# camera.net
KiCad netlist of a schematic drawn in Altium Designer
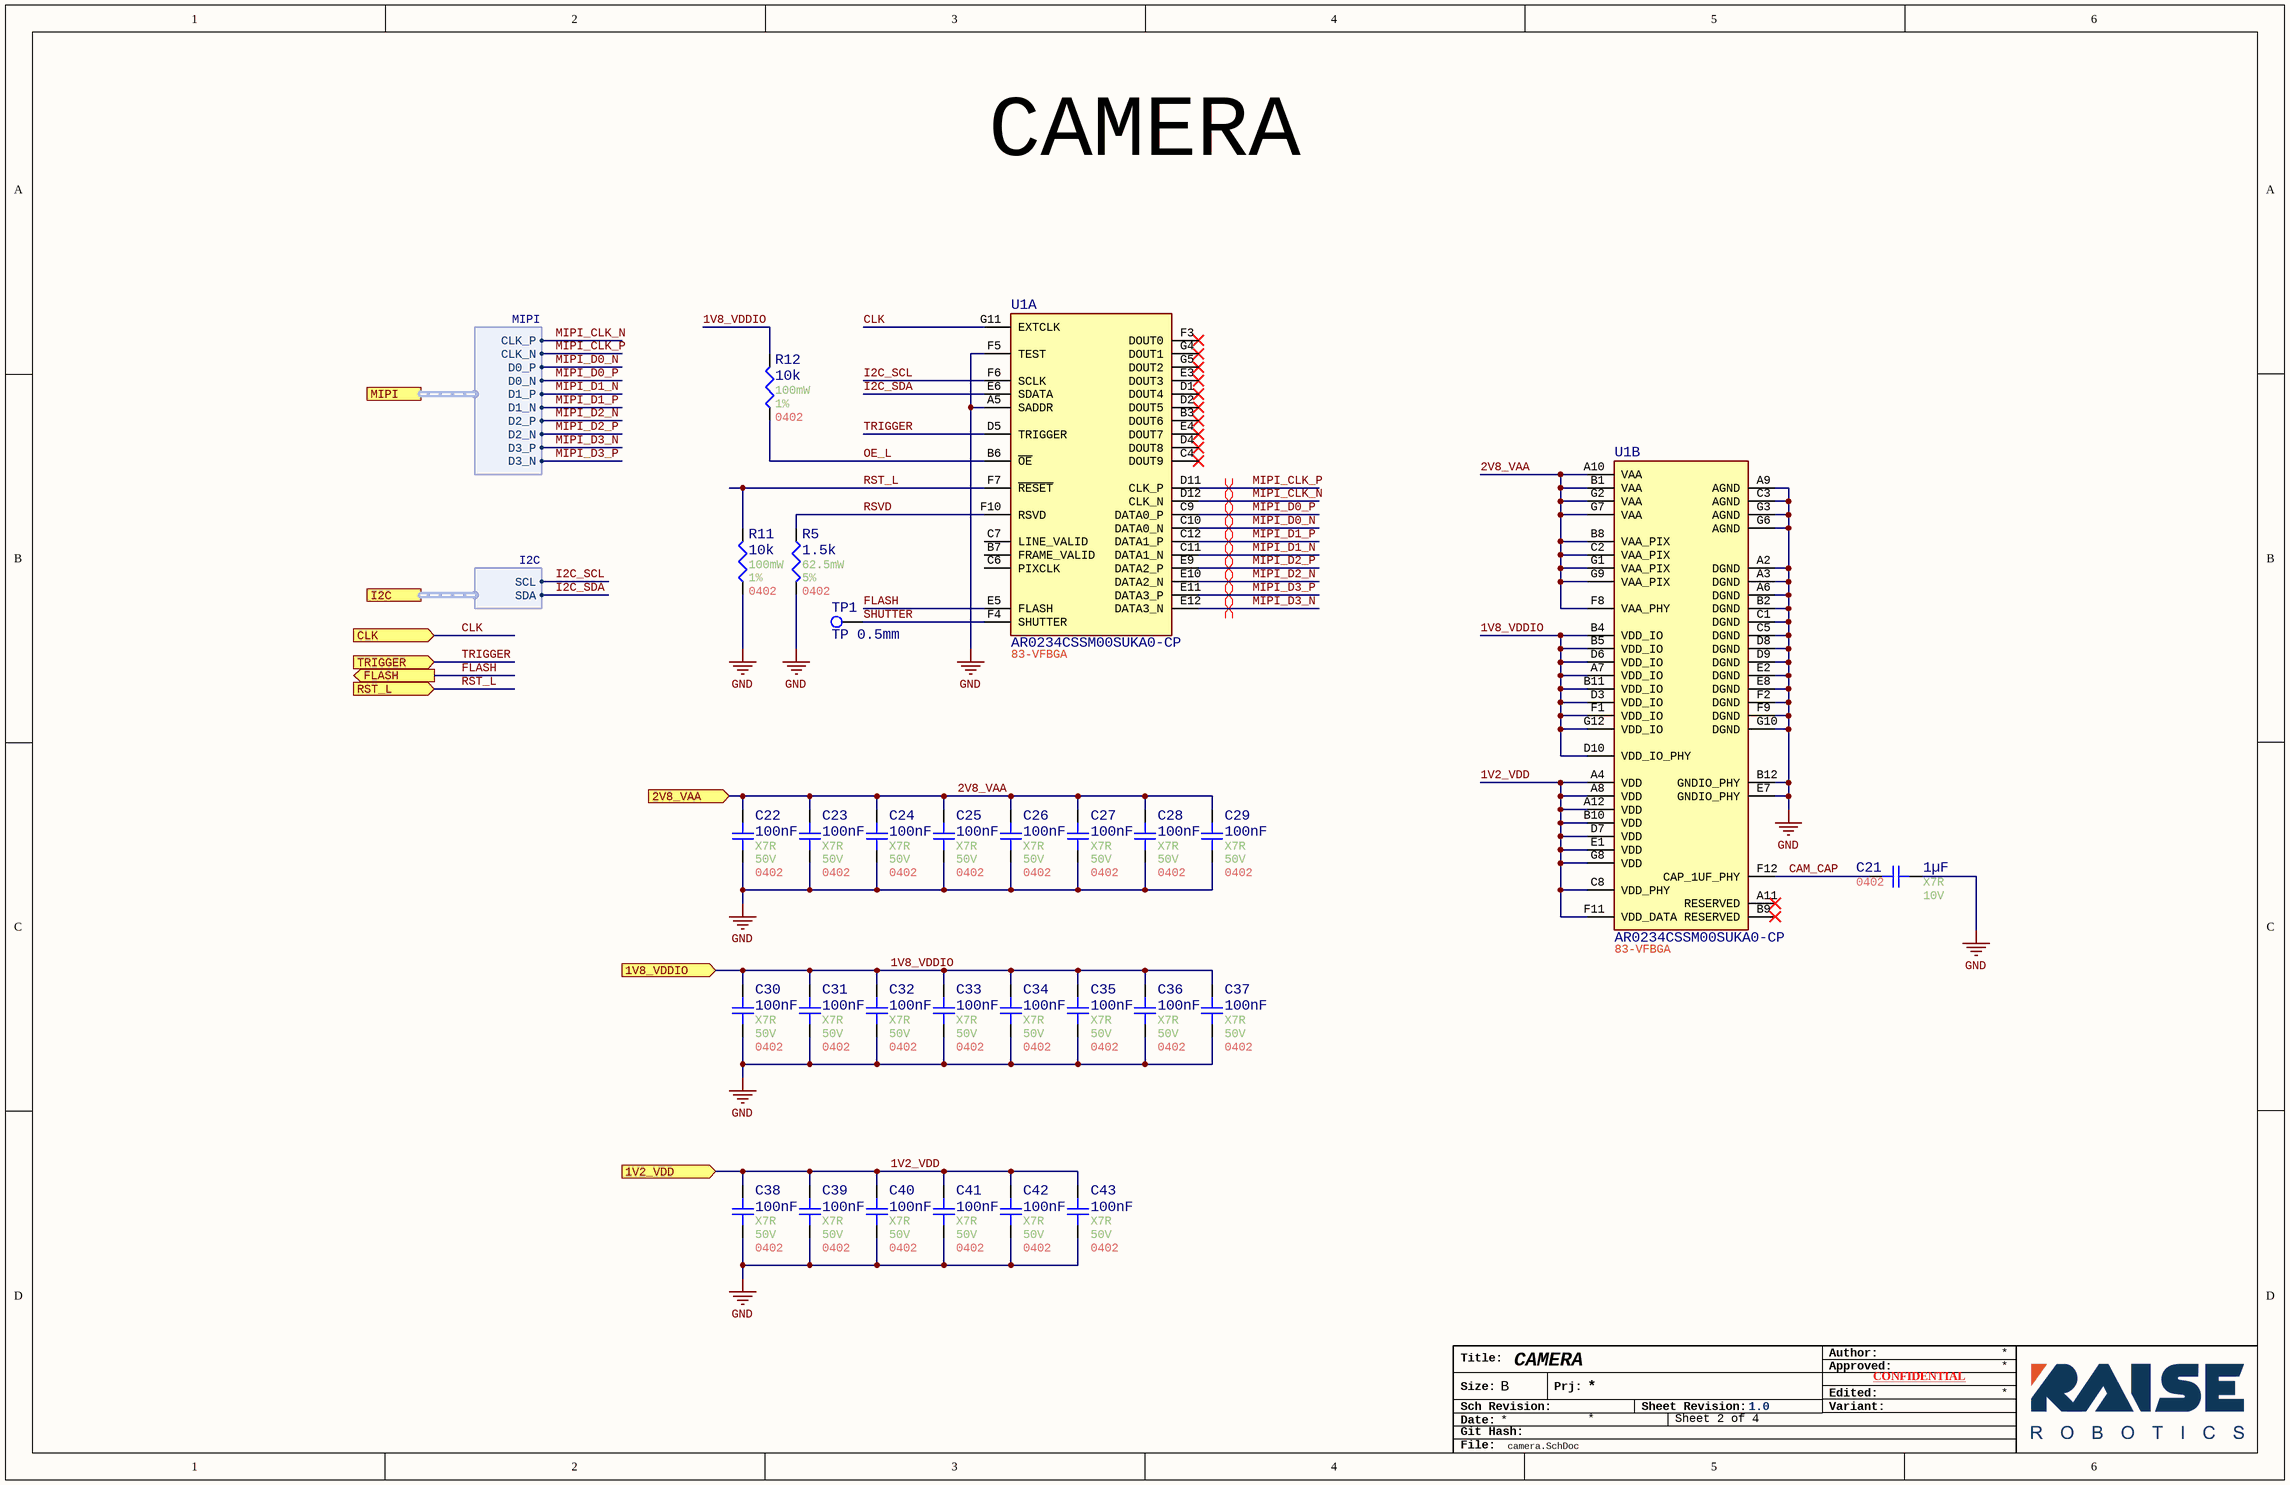
[diagram p0: camera.SchDoc]

(export (version "E")
  (design (tool "Eeschema 10.0.6"))
  (components
    (comp (ref "C21")
      (value "1µF")
      (footprint "Generic 0402 capacitor")
      (description "Cap Cer 1UF 20V X7T 0402")
      (fields
        (field (name "TEMPERATURE COEFFICIENT") "X7R")
        (field (name "VOLTAGE RATING") "10V")
        (field (name "CASE/PACKAGE") "0402")
        (field (name "TOLERANCE") "20%")
        (field (name "Comment") "MAASL105CD7105MFCA01")
      )
      (libsource (lib "Raise Robotics") (part "Unpolarized Capacitor"))
    )
    (comp (ref "C22")
      (value "100nF")
      (footprint "Generic 0402 capacitor")
      (fields
        (field (name "TEMPERATURE COEFFICIENT") "X7R")
        (field (name "VOLTAGE RATING") "50V")
        (field (name "CASE/PACKAGE") "0402")
        (field (name "TOLERANCE") "10%")
        (field (name "Comment") "GRT155R71H104KE01D")
      )
      (libsource (lib "Raise Robotics") (part "Unpolarized Capacitor"))
    )
    (comp (ref "C23")
      (value "100nF")
      (footprint "Generic 0402 capacitor")
      (fields
        (field (name "TEMPERATURE COEFFICIENT") "X7R")
        (field (name "VOLTAGE RATING") "50V")
        (field (name "CASE/PACKAGE") "0402")
        (field (name "TOLERANCE") "10%")
        (field (name "Comment") "GRT155R71H104KE01D")
      )
      (libsource (lib "Raise Robotics") (part "Unpolarized Capacitor"))
    )
    (comp (ref "C24")
      (value "100nF")
      (footprint "Generic 0402 capacitor")
      (fields
        (field (name "TEMPERATURE COEFFICIENT") "X7R")
        (field (name "VOLTAGE RATING") "50V")
        (field (name "CASE/PACKAGE") "0402")
        (field (name "TOLERANCE") "10%")
        (field (name "Comment") "GRT155R71H104KE01D")
      )
      (libsource (lib "Raise Robotics") (part "Unpolarized Capacitor"))
    )
    (comp (ref "C25")
      (value "100nF")
      (footprint "Generic 0402 capacitor")
      (fields
        (field (name "TEMPERATURE COEFFICIENT") "X7R")
        (field (name "VOLTAGE RATING") "50V")
        (field (name "CASE/PACKAGE") "0402")
        (field (name "TOLERANCE") "10%")
        (field (name "Comment") "GRT155R71H104KE01D")
      )
      (libsource (lib "Raise Robotics") (part "Unpolarized Capacitor"))
    )
    (comp (ref "C26")
      (value "100nF")
      (footprint "Generic 0402 capacitor")
      (fields
        (field (name "TEMPERATURE COEFFICIENT") "X7R")
        (field (name "VOLTAGE RATING") "50V")
        (field (name "CASE/PACKAGE") "0402")
        (field (name "TOLERANCE") "10%")
        (field (name "Comment") "GRT155R71H104KE01D")
      )
      (libsource (lib "Raise Robotics") (part "Unpolarized Capacitor"))
    )
    (comp (ref "C27")
      (value "100nF")
      (footprint "Generic 0402 capacitor")
      (fields
        (field (name "TEMPERATURE COEFFICIENT") "X7R")
        (field (name "VOLTAGE RATING") "50V")
        (field (name "CASE/PACKAGE") "0402")
        (field (name "TOLERANCE") "10%")
        (field (name "Comment") "GRT155R71H104KE01D")
      )
      (libsource (lib "Raise Robotics") (part "Unpolarized Capacitor"))
    )
    (comp (ref "C28")
      (value "100nF")
      (footprint "Generic 0402 capacitor")
      (fields
        (field (name "TEMPERATURE COEFFICIENT") "X7R")
        (field (name "VOLTAGE RATING") "50V")
        (field (name "CASE/PACKAGE") "0402")
        (field (name "TOLERANCE") "10%")
        (field (name "Comment") "GRT155R71H104KE01D")
      )
      (libsource (lib "Raise Robotics") (part "Unpolarized Capacitor"))
    )
    (comp (ref "C29")
      (value "100nF")
      (footprint "Generic 0402 capacitor")
      (fields
        (field (name "TEMPERATURE COEFFICIENT") "X7R")
        (field (name "VOLTAGE RATING") "50V")
        (field (name "CASE/PACKAGE") "0402")
        (field (name "TOLERANCE") "10%")
        (field (name "Comment") "GRT155R71H104KE01D")
      )
      (libsource (lib "Raise Robotics") (part "Unpolarized Capacitor"))
    )
    (comp (ref "C30")
      (value "100nF")
      (footprint "Generic 0402 capacitor")
      (fields
        (field (name "TEMPERATURE COEFFICIENT") "X7R")
        (field (name "VOLTAGE RATING") "50V")
        (field (name "CASE/PACKAGE") "0402")
        (field (name "TOLERANCE") "10%")
        (field (name "Comment") "GRT155R71H104KE01D")
      )
      (libsource (lib "Raise Robotics") (part "Unpolarized Capacitor"))
    )
    (comp (ref "C31")
      (value "100nF")
      (footprint "Generic 0402 capacitor")
      (fields
        (field (name "TEMPERATURE COEFFICIENT") "X7R")
        (field (name "VOLTAGE RATING") "50V")
        (field (name "CASE/PACKAGE") "0402")
        (field (name "TOLERANCE") "10%")
        (field (name "Comment") "GRT155R71H104KE01D")
      )
      (libsource (lib "Raise Robotics") (part "Unpolarized Capacitor"))
    )
    (comp (ref "C32")
      (value "100nF")
      (footprint "Generic 0402 capacitor")
      (fields
        (field (name "TEMPERATURE COEFFICIENT") "X7R")
        (field (name "VOLTAGE RATING") "50V")
        (field (name "CASE/PACKAGE") "0402")
        (field (name "TOLERANCE") "10%")
        (field (name "Comment") "GRT155R71H104KE01D")
      )
      (libsource (lib "Raise Robotics") (part "Unpolarized Capacitor"))
    )
    (comp (ref "C33")
      (value "100nF")
      (footprint "Generic 0402 capacitor")
      (fields
        (field (name "TEMPERATURE COEFFICIENT") "X7R")
        (field (name "VOLTAGE RATING") "50V")
        (field (name "CASE/PACKAGE") "0402")
        (field (name "TOLERANCE") "10%")
        (field (name "Comment") "GRT155R71H104KE01D")
      )
      (libsource (lib "Raise Robotics") (part "Unpolarized Capacitor"))
    )
    (comp (ref "C34")
      (value "100nF")
      (footprint "Generic 0402 capacitor")
      (fields
        (field (name "TEMPERATURE COEFFICIENT") "X7R")
        (field (name "VOLTAGE RATING") "50V")
        (field (name "CASE/PACKAGE") "0402")
        (field (name "TOLERANCE") "10%")
        (field (name "Comment") "GRT155R71H104KE01D")
      )
      (libsource (lib "Raise Robotics") (part "Unpolarized Capacitor"))
    )
    (comp (ref "C35")
      (value "100nF")
      (footprint "Generic 0402 capacitor")
      (fields
        (field (name "TEMPERATURE COEFFICIENT") "X7R")
        (field (name "VOLTAGE RATING") "50V")
        (field (name "CASE/PACKAGE") "0402")
        (field (name "TOLERANCE") "10%")
        (field (name "Comment") "GRT155R71H104KE01D")
      )
      (libsource (lib "Raise Robotics") (part "Unpolarized Capacitor"))
    )
    (comp (ref "C36")
      (value "100nF")
      (footprint "Generic 0402 capacitor")
      (fields
        (field (name "TEMPERATURE COEFFICIENT") "X7R")
        (field (name "VOLTAGE RATING") "50V")
        (field (name "CASE/PACKAGE") "0402")
        (field (name "TOLERANCE") "10%")
        (field (name "Comment") "GRT155R71H104KE01D")
      )
      (libsource (lib "Raise Robotics") (part "Unpolarized Capacitor"))
    )
    (comp (ref "C37")
      (value "100nF")
      (footprint "Generic 0402 capacitor")
      (fields
        (field (name "TEMPERATURE COEFFICIENT") "X7R")
        (field (name "VOLTAGE RATING") "50V")
        (field (name "CASE/PACKAGE") "0402")
        (field (name "TOLERANCE") "10%")
        (field (name "Comment") "GRT155R71H104KE01D")
      )
      (libsource (lib "Raise Robotics") (part "Unpolarized Capacitor"))
    )
    (comp (ref "C38")
      (value "100nF")
      (footprint "Generic 0402 capacitor")
      (fields
        (field (name "TEMPERATURE COEFFICIENT") "X7R")
        (field (name "VOLTAGE RATING") "50V")
        (field (name "CASE/PACKAGE") "0402")
        (field (name "TOLERANCE") "10%")
        (field (name "Comment") "GRT155R71H104KE01D")
      )
      (libsource (lib "Raise Robotics") (part "Unpolarized Capacitor"))
    )
    (comp (ref "C39")
      (value "100nF")
      (footprint "Generic 0402 capacitor")
      (fields
        (field (name "TEMPERATURE COEFFICIENT") "X7R")
        (field (name "VOLTAGE RATING") "50V")
        (field (name "CASE/PACKAGE") "0402")
        (field (name "TOLERANCE") "10%")
        (field (name "Comment") "GRT155R71H104KE01D")
      )
      (libsource (lib "Raise Robotics") (part "Unpolarized Capacitor"))
    )
    (comp (ref "C40")
      (value "100nF")
      (footprint "Generic 0402 capacitor")
      (fields
        (field (name "TEMPERATURE COEFFICIENT") "X7R")
        (field (name "VOLTAGE RATING") "50V")
        (field (name "CASE/PACKAGE") "0402")
        (field (name "TOLERANCE") "10%")
        (field (name "Comment") "GRT155R71H104KE01D")
      )
      (libsource (lib "Raise Robotics") (part "Unpolarized Capacitor"))
    )
    (comp (ref "C41")
      (value "100nF")
      (footprint "Generic 0402 capacitor")
      (fields
        (field (name "TEMPERATURE COEFFICIENT") "X7R")
        (field (name "VOLTAGE RATING") "50V")
        (field (name "CASE/PACKAGE") "0402")
        (field (name "TOLERANCE") "10%")
        (field (name "Comment") "GRT155R71H104KE01D")
      )
      (libsource (lib "Raise Robotics") (part "Unpolarized Capacitor"))
    )
    (comp (ref "C42")
      (value "100nF")
      (footprint "Generic 0402 capacitor")
      (fields
        (field (name "TEMPERATURE COEFFICIENT") "X7R")
        (field (name "VOLTAGE RATING") "50V")
        (field (name "CASE/PACKAGE") "0402")
        (field (name "TOLERANCE") "10%")
        (field (name "Comment") "GRT155R71H104KE01D")
      )
      (libsource (lib "Raise Robotics") (part "Unpolarized Capacitor"))
    )
    (comp (ref "C43")
      (value "100nF")
      (footprint "Generic 0402 capacitor")
      (fields
        (field (name "TEMPERATURE COEFFICIENT") "X7R")
        (field (name "VOLTAGE RATING") "50V")
        (field (name "CASE/PACKAGE") "0402")
        (field (name "TOLERANCE") "10%")
        (field (name "Comment") "GRT155R71H104KE01D")
      )
      (libsource (lib "Raise Robotics") (part "Unpolarized Capacitor"))
    )
    (comp (ref "R5")
      (value "1.5k")
      (footprint "Generic 0402 Resistor")
      (description "Res Thick Film 0402 1.5K Ohm 5% 0.063W ±100ppm/°C Molded SMD Paper T/R")
      (fields
        (field (name "POWER") "62.5mW")
        (field (name "TOLERANCE") "5%")
        (field (name "CASE/PACKAGE") "0402")
        (field (name "Comment") "RMCF0402JT1K50")
      )
      (libsource (lib "Raise Robotics") (part "Resistor"))
    )
    (comp (ref "R11")
      (value "10k")
      (footprint "Generic 0402 Resistor")
      (description "Fixed Resistor, Thin Film, 0.1W, 10000ohm, 50V, 1% +/-Tol, 100ppm/Cel, Surface Mount, 0402")
      (fields
        (field (name "POWER") "100mW")
        (field (name "TOLERANCE") "1%")
        (field (name "CASE/PACKAGE") "0402")
        (field (name "MANUFACTURER PART NUMBER") "Blank")
        (field (name "Comment") "RNCP0402FTD10K0")
      )
      (libsource (lib "Raise Robotics") (part "Resistor"))
    )
    (comp (ref "R12")
      (value "10k")
      (footprint "Generic 0402 Resistor")
      (description "Fixed Resistor, Thin Film, 0.1W, 10000ohm, 50V, 1% +/-Tol, 100ppm/Cel, Surface Mount, 0402")
      (fields
        (field (name "POWER") "100mW")
        (field (name "TOLERANCE") "1%")
        (field (name "CASE/PACKAGE") "0402")
        (field (name "MANUFACTURER PART NUMBER") "Blank")
        (field (name "Comment") "RNCP0402FTD10K0")
      )
      (libsource (lib "Raise Robotics") (part "Resistor"))
    )
    (comp (ref "TP1")
      (value "TP 0.5mm")
      (footprint "TP 0.5mm")
      (description "0.5mm circular test point")
      (libsource (lib "Raise Robotics") (part "Test Point"))
    )
    (comp (ref "U1")
      (value "AR0234CSSM00SUKA0-CP")
      (footprint "83-VFBGA")
      (description "1/2.6-inch 2.3 Mp CMOS Digital Image Sensor with Global Shutter 2.3MP 1/2.6, Mono, 0 deg CRA")
      (fields (field (name "MPN") "TJA1051TK/3/1J") (field (name "CASE/PACKAGE") "83-VFBGA"))
      (libsource (lib "Raise Robotics") (part "AR0234CSSM00SUKA0-CP"))
    )
  )
  (nets
    (net (code "3") (name "/1V2_VDD") (class "Default")
      (node (ref "C38") (pin "2") (pinfunction "2_2") (pintype "passive"))
      (node (ref "C39") (pin "2") (pinfunction "2_2") (pintype "passive"))
      (node (ref "C40") (pin "2") (pinfunction "2_2") (pintype "passive"))
      (node (ref "C41") (pin "2") (pinfunction "2_2") (pintype "passive"))
      (node (ref "C42") (pin "2") (pinfunction "2_2") (pintype "passive"))
      (node (ref "C43") (pin "2") (pinfunction "2_2") (pintype "passive"))
      (node (ref "U1") (pin "A12") (pinfunction "VDD_A12") (pintype "passive"))
      (node (ref "U1") (pin "A4") (pinfunction "VDD_A4") (pintype "passive"))
      (node (ref "U1") (pin "A8") (pinfunction "VDD_A8") (pintype "passive"))
      (node (ref "U1") (pin "B10") (pinfunction "VDD_B10") (pintype "passive"))
      (node (ref "U1") (pin "C8") (pinfunction "VDD_PHY_C8") (pintype "passive"))
      (node (ref "U1") (pin "D7") (pinfunction "VDD_D7") (pintype "passive"))
      (node (ref "U1") (pin "E1") (pinfunction "VDD_E1") (pintype "passive"))
      (node (ref "U1") (pin "F11") (pinfunction "VDD_DATA_F11") (pintype "passive"))
      (node (ref "U1") (pin "G8") (pinfunction "VDD_G8") (pintype "passive"))
    )
    (net (code "4") (name "/1V8_VDDIO") (class "Default")
      (node (ref "C30") (pin "2") (pinfunction "2_2") (pintype "passive"))
      (node (ref "C31") (pin "2") (pinfunction "2_2") (pintype "passive"))
      (node (ref "C32") (pin "2") (pinfunction "2_2") (pintype "passive"))
      (node (ref "C33") (pin "2") (pinfunction "2_2") (pintype "passive"))
      (node (ref "C34") (pin "2") (pinfunction "2_2") (pintype "passive"))
      (node (ref "C35") (pin "2") (pinfunction "2_2") (pintype "passive"))
      (node (ref "C36") (pin "2") (pinfunction "2_2") (pintype "passive"))
      (node (ref "C37") (pin "2") (pinfunction "2_2") (pintype "passive"))
      (node (ref "R12") (pin "2") (pinfunction "2_2") (pintype "passive"))
      (node (ref "U1") (pin "A7") (pinfunction "VDD_IO_A7") (pintype "passive"))
      (node (ref "U1") (pin "B11") (pinfunction "VDD_IO_B11") (pintype "passive"))
      (node (ref "U1") (pin "B4") (pinfunction "VDD_IO_B4") (pintype "passive"))
      (node (ref "U1") (pin "B5") (pinfunction "VDD_IO_B5") (pintype "passive"))
      (node (ref "U1") (pin "D10") (pinfunction "VDD_IO_PHY_D10") (pintype "passive"))
      (node (ref "U1") (pin "D3") (pinfunction "VDD_IO_D3") (pintype "passive"))
      (node (ref "U1") (pin "D6") (pinfunction "VDD_IO_D6") (pintype "passive"))
      (node (ref "U1") (pin "F1") (pinfunction "VDD_IO_F1") (pintype "passive"))
      (node (ref "U1") (pin "G12") (pinfunction "VDD_IO_G12") (pintype "passive"))
    )
    (net (code "5") (name "/2V8_VAA") (class "Default")
      (node (ref "C22") (pin "2") (pinfunction "2_2") (pintype "passive"))
      (node (ref "C23") (pin "2") (pinfunction "2_2") (pintype "passive"))
      (node (ref "C24") (pin "2") (pinfunction "2_2") (pintype "passive"))
      (node (ref "C25") (pin "2") (pinfunction "2_2") (pintype "passive"))
      (node (ref "C26") (pin "2") (pinfunction "2_2") (pintype "passive"))
      (node (ref "C27") (pin "2") (pinfunction "2_2") (pintype "passive"))
      (node (ref "C28") (pin "2") (pinfunction "2_2") (pintype "passive"))
      (node (ref "C29") (pin "2") (pinfunction "2_2") (pintype "passive"))
      (node (ref "U1") (pin "A10") (pinfunction "VAA_A10") (pintype "passive"))
      (node (ref "U1") (pin "B1") (pinfunction "VAA_B1") (pintype "passive"))
      (node (ref "U1") (pin "B8") (pinfunction "VAA_PIX_B8") (pintype "passive"))
      (node (ref "U1") (pin "C2") (pinfunction "VAA_PIX_C2") (pintype "passive"))
      (node (ref "U1") (pin "F8") (pinfunction "VAA_PHY_F8") (pintype "passive"))
      (node (ref "U1") (pin "G1") (pinfunction "VAA_PIX_G1") (pintype "passive"))
      (node (ref "U1") (pin "G2") (pinfunction "VAA_G2") (pintype "passive"))
      (node (ref "U1") (pin "G7") (pinfunction "VAA_G7") (pintype "passive"))
      (node (ref "U1") (pin "G9") (pinfunction "VAA_PIX_G9") (pintype "passive"))
    )
    (net (code "6") (name "/CAM_CAP") (class "Default")
      (node (ref "C21") (pin "2") (pinfunction "2_2") (pintype "passive"))
      (node (ref "U1") (pin "F12") (pinfunction "CAP_1UF_PHY_F12") (pintype "passive"))
    )
    (net (code "7") (name "/CLK") (class "Default")
      (node (ref "U1") (pin "G11") (pinfunction "EXTCLK_G11") (pintype "passive"))
    )
    (net (code "8") (name "/FLASH") (class "Default")
      (node (ref "U1") (pin "E5") (pinfunction "FLASH_E5") (pintype "passive"))
    )
    (net (code "9") (name "/I2C_SCL") (class "Default")
      (node (ref "U1") (pin "F6") (pinfunction "SCLK_F6") (pintype "passive"))
    )
    (net (code "10") (name "/I2C_SDA") (class "Default")
      (node (ref "U1") (pin "E6") (pinfunction "SDATA_E6") (pintype "passive"))
    )
    (net (code "11") (name "/MIPI_CLK_N") (class "Default")
      (node (ref "U1") (pin "D12") (pinfunction "CLK_N_D12") (pintype "passive"))
    )
    (net (code "12") (name "/MIPI_CLK_P") (class "Default")
      (node (ref "U1") (pin "D11") (pinfunction "CLK_P_D11") (pintype "passive"))
    )
    (net (code "13") (name "/MIPI_D0_N") (class "Default")
      (node (ref "U1") (pin "C10") (pinfunction "DATA0_N_C10") (pintype "passive"))
    )
    (net (code "14") (name "/MIPI_D0_P") (class "Default")
      (node (ref "U1") (pin "C9") (pinfunction "DATA0_P_C9") (pintype "passive"))
    )
    (net (code "15") (name "/MIPI_D1_N") (class "Default")
      (node (ref "U1") (pin "C11") (pinfunction "DATA1_N_C11") (pintype "passive"))
    )
    (net (code "16") (name "/MIPI_D1_P") (class "Default")
      (node (ref "U1") (pin "C12") (pinfunction "DATA1_P_C12") (pintype "passive"))
    )
    (net (code "17") (name "/MIPI_D2_N") (class "Default")
      (node (ref "U1") (pin "E10") (pinfunction "DATA2_N_E10") (pintype "passive"))
    )
    (net (code "18") (name "/MIPI_D2_P") (class "Default")
      (node (ref "U1") (pin "E9") (pinfunction "DATA2_P_E9") (pintype "passive"))
    )
    (net (code "19") (name "/MIPI_D3_N") (class "Default")
      (node (ref "U1") (pin "E12") (pinfunction "DATA3_N_E12") (pintype "passive"))
    )
    (net (code "20") (name "/MIPI_D3_P") (class "Default")
      (node (ref "U1") (pin "E11") (pinfunction "DATA3_P_E11") (pintype "passive"))
    )
    (net (code "21") (name "/OE_L") (class "Default")
      (node (ref "R12") (pin "1") (pinfunction "1_1") (pintype "passive"))
      (node (ref "U1") (pin "B6") (pinfunction "~{OE}_B6") (pintype "passive"))
    )
    (net (code "22") (name "/RST_L") (class "Default")
      (node (ref "R11") (pin "2") (pinfunction "2_2") (pintype "passive"))
      (node (ref "U1") (pin "F7") (pinfunction "~{RESET}_F7") (pintype "passive"))
    )
    (net (code "23") (name "/RSVD") (class "Default")
      (node (ref "R5") (pin "1") (pinfunction "1_1") (pintype "passive"))
      (node (ref "U1") (pin "F10") (pinfunction "RSVD_F10") (pintype "passive"))
    )
    (net (code "24") (name "/SHUTTER") (class "Default")
      (node (ref "TP1") (pin "1") (pinfunction "1_1") (pintype "passive"))
      (node (ref "U1") (pin "F4") (pinfunction "SHUTTER_F4") (pintype "passive"))
    )
    (net (code "25") (name "/TRIGGER") (class "Default")
      (node (ref "U1") (pin "D5") (pinfunction "TRIGGER_D5") (pintype "passive"))
    )
    (net (code "28") (name "GND") (class "Default")
      (node (ref "C21") (pin "1") (pinfunction "1_1") (pintype "passive"))
      (node (ref "C22") (pin "1") (pinfunction "1_1") (pintype "passive"))
      (node (ref "C23") (pin "1") (pinfunction "1_1") (pintype "passive"))
      (node (ref "C24") (pin "1") (pinfunction "1_1") (pintype "passive"))
      (node (ref "C25") (pin "1") (pinfunction "1_1") (pintype "passive"))
      (node (ref "C26") (pin "1") (pinfunction "1_1") (pintype "passive"))
      (node (ref "C27") (pin "1") (pinfunction "1_1") (pintype "passive"))
      (node (ref "C28") (pin "1") (pinfunction "1_1") (pintype "passive"))
      (node (ref "C29") (pin "1") (pinfunction "1_1") (pintype "passive"))
      (node (ref "C30") (pin "1") (pinfunction "1_1") (pintype "passive"))
      (node (ref "C31") (pin "1") (pinfunction "1_1") (pintype "passive"))
      (node (ref "C32") (pin "1") (pinfunction "1_1") (pintype "passive"))
      (node (ref "C33") (pin "1") (pinfunction "1_1") (pintype "passive"))
      (node (ref "C34") (pin "1") (pinfunction "1_1") (pintype "passive"))
      (node (ref "C35") (pin "1") (pinfunction "1_1") (pintype "passive"))
      (node (ref "C36") (pin "1") (pinfunction "1_1") (pintype "passive"))
      (node (ref "C37") (pin "1") (pinfunction "1_1") (pintype "passive"))
      (node (ref "C38") (pin "1") (pinfunction "1_1") (pintype "passive"))
      (node (ref "C39") (pin "1") (pinfunction "1_1") (pintype "passive"))
      (node (ref "C40") (pin "1") (pinfunction "1_1") (pintype "passive"))
      (node (ref "C41") (pin "1") (pinfunction "1_1") (pintype "passive"))
      (node (ref "C42") (pin "1") (pinfunction "1_1") (pintype "passive"))
      (node (ref "C43") (pin "1") (pinfunction "1_1") (pintype "passive"))
      (node (ref "R11") (pin "1") (pinfunction "1_1") (pintype "passive"))
      (node (ref "R5") (pin "2") (pinfunction "2_2") (pintype "passive"))
      (node (ref "U1") (pin "A2") (pinfunction "DGND_A2") (pintype "passive"))
      (node (ref "U1") (pin "A3") (pinfunction "DGND_A3") (pintype "passive"))
      (node (ref "U1") (pin "A5") (pinfunction "SADDR_A5") (pintype "passive"))
      (node (ref "U1") (pin "A6") (pinfunction "DGND_A6") (pintype "passive"))
      (node (ref "U1") (pin "A9") (pinfunction "AGND_A9") (pintype "passive"))
      (node (ref "U1") (pin "B12") (pinfunction "GNDIO_PHY_B12") (pintype "passive"))
      (node (ref "U1") (pin "B2") (pinfunction "DGND_B2") (pintype "passive"))
      (node (ref "U1") (pin "C1") (pinfunction "DGND_C1") (pintype "passive"))
      (node (ref "U1") (pin "C3") (pinfunction "AGND_C3") (pintype "passive"))
      (node (ref "U1") (pin "C5") (pinfunction "DGND_C5") (pintype "passive"))
      (node (ref "U1") (pin "D8") (pinfunction "DGND_D8") (pintype "passive"))
      (node (ref "U1") (pin "D9") (pinfunction "DGND_D9") (pintype "passive"))
      (node (ref "U1") (pin "E2") (pinfunction "DGND_E2") (pintype "passive"))
      (node (ref "U1") (pin "E7") (pinfunction "GNDIO_PHY_E7") (pintype "passive"))
      (node (ref "U1") (pin "E8") (pinfunction "DGND_E8") (pintype "passive"))
      (node (ref "U1") (pin "F2") (pinfunction "DGND_F2") (pintype "passive"))
      (node (ref "U1") (pin "F5") (pinfunction "TEST_F5") (pintype "passive"))
      (node (ref "U1") (pin "F9") (pinfunction "DGND_F9") (pintype "passive"))
      (node (ref "U1") (pin "G10") (pinfunction "DGND_G10") (pintype "passive"))
      (node (ref "U1") (pin "G3") (pinfunction "AGND_G3") (pintype "passive"))
      (node (ref "U1") (pin "G6") (pinfunction "AGND_G6") (pintype "passive"))
    )
    (net (code "29") (name "unconnected-(U1A-DOUT0-PadF3)") (class "Default")
      (node (ref "U1") (pin "F3") (pinfunction "DOUT0_F3") (pintype "passive+no_connect"))
    )
    (net (code "30") (name "unconnected-(U1A-DOUT1-PadG4)") (class "Default")
      (node (ref "U1") (pin "G4") (pinfunction "DOUT1_G4") (pintype "passive+no_connect"))
    )
    (net (code "31") (name "unconnected-(U1A-DOUT2-PadG5)") (class "Default")
      (node (ref "U1") (pin "G5") (pinfunction "DOUT2_G5") (pintype "passive+no_connect"))
    )
    (net (code "32") (name "unconnected-(U1A-DOUT3-PadE3)") (class "Default")
      (node (ref "U1") (pin "E3") (pinfunction "DOUT3_E3") (pintype "passive+no_connect"))
    )
    (net (code "33") (name "unconnected-(U1A-DOUT4-PadD1)") (class "Default")
      (node (ref "U1") (pin "D1") (pinfunction "DOUT4_D1") (pintype "passive+no_connect"))
    )
    (net (code "34") (name "unconnected-(U1A-DOUT5-PadD2)") (class "Default")
      (node (ref "U1") (pin "D2") (pinfunction "DOUT5_D2") (pintype "passive+no_connect"))
    )
    (net (code "35") (name "unconnected-(U1A-DOUT6-PadB3)") (class "Default")
      (node (ref "U1") (pin "B3") (pinfunction "DOUT6_B3") (pintype "passive+no_connect"))
    )
    (net (code "36") (name "unconnected-(U1A-DOUT7-PadE4)") (class "Default")
      (node (ref "U1") (pin "E4") (pinfunction "DOUT7_E4") (pintype "passive+no_connect"))
    )
    (net (code "37") (name "unconnected-(U1A-DOUT8-PadD4)") (class "Default")
      (node (ref "U1") (pin "D4") (pinfunction "DOUT8_D4") (pintype "passive+no_connect"))
    )
    (net (code "38") (name "unconnected-(U1A-DOUT9-PadC4)") (class "Default")
      (node (ref "U1") (pin "C4") (pinfunction "DOUT9_C4") (pintype "passive+no_connect"))
    )
    (net (code "39") (name "unconnected-(U1A-FRAME_VALID-PadB7)") (class "Default")
      (node (ref "U1") (pin "B7") (pinfunction "FRAME_VALID_B7") (pintype "passive"))
    )
    (net (code "40") (name "unconnected-(U1A-LINE_VALID-PadC7)") (class "Default")
      (node (ref "U1") (pin "C7") (pinfunction "LINE_VALID_C7") (pintype "passive"))
    )
    (net (code "41") (name "unconnected-(U1A-PIXCLK-PadC6)") (class "Default")
      (node (ref "U1") (pin "C6") (pinfunction "PIXCLK_C6") (pintype "passive"))
    )
    (net (code "42") (name "unconnected-(U1B-RESERVED-PadA11)") (class "Default")
      (node (ref "U1") (pin "A11") (pinfunction "RESERVED_A11") (pintype "passive+no_connect"))
    )
    (net (code "43") (name "unconnected-(U1B-RESERVED-PadB9)") (class "Default")
      (node (ref "U1") (pin "B9") (pinfunction "RESERVED_B9") (pintype "passive+no_connect"))
    )
  )
)
